# wmrp.net
KiCad netlist of a schematic drawn in EAGLE
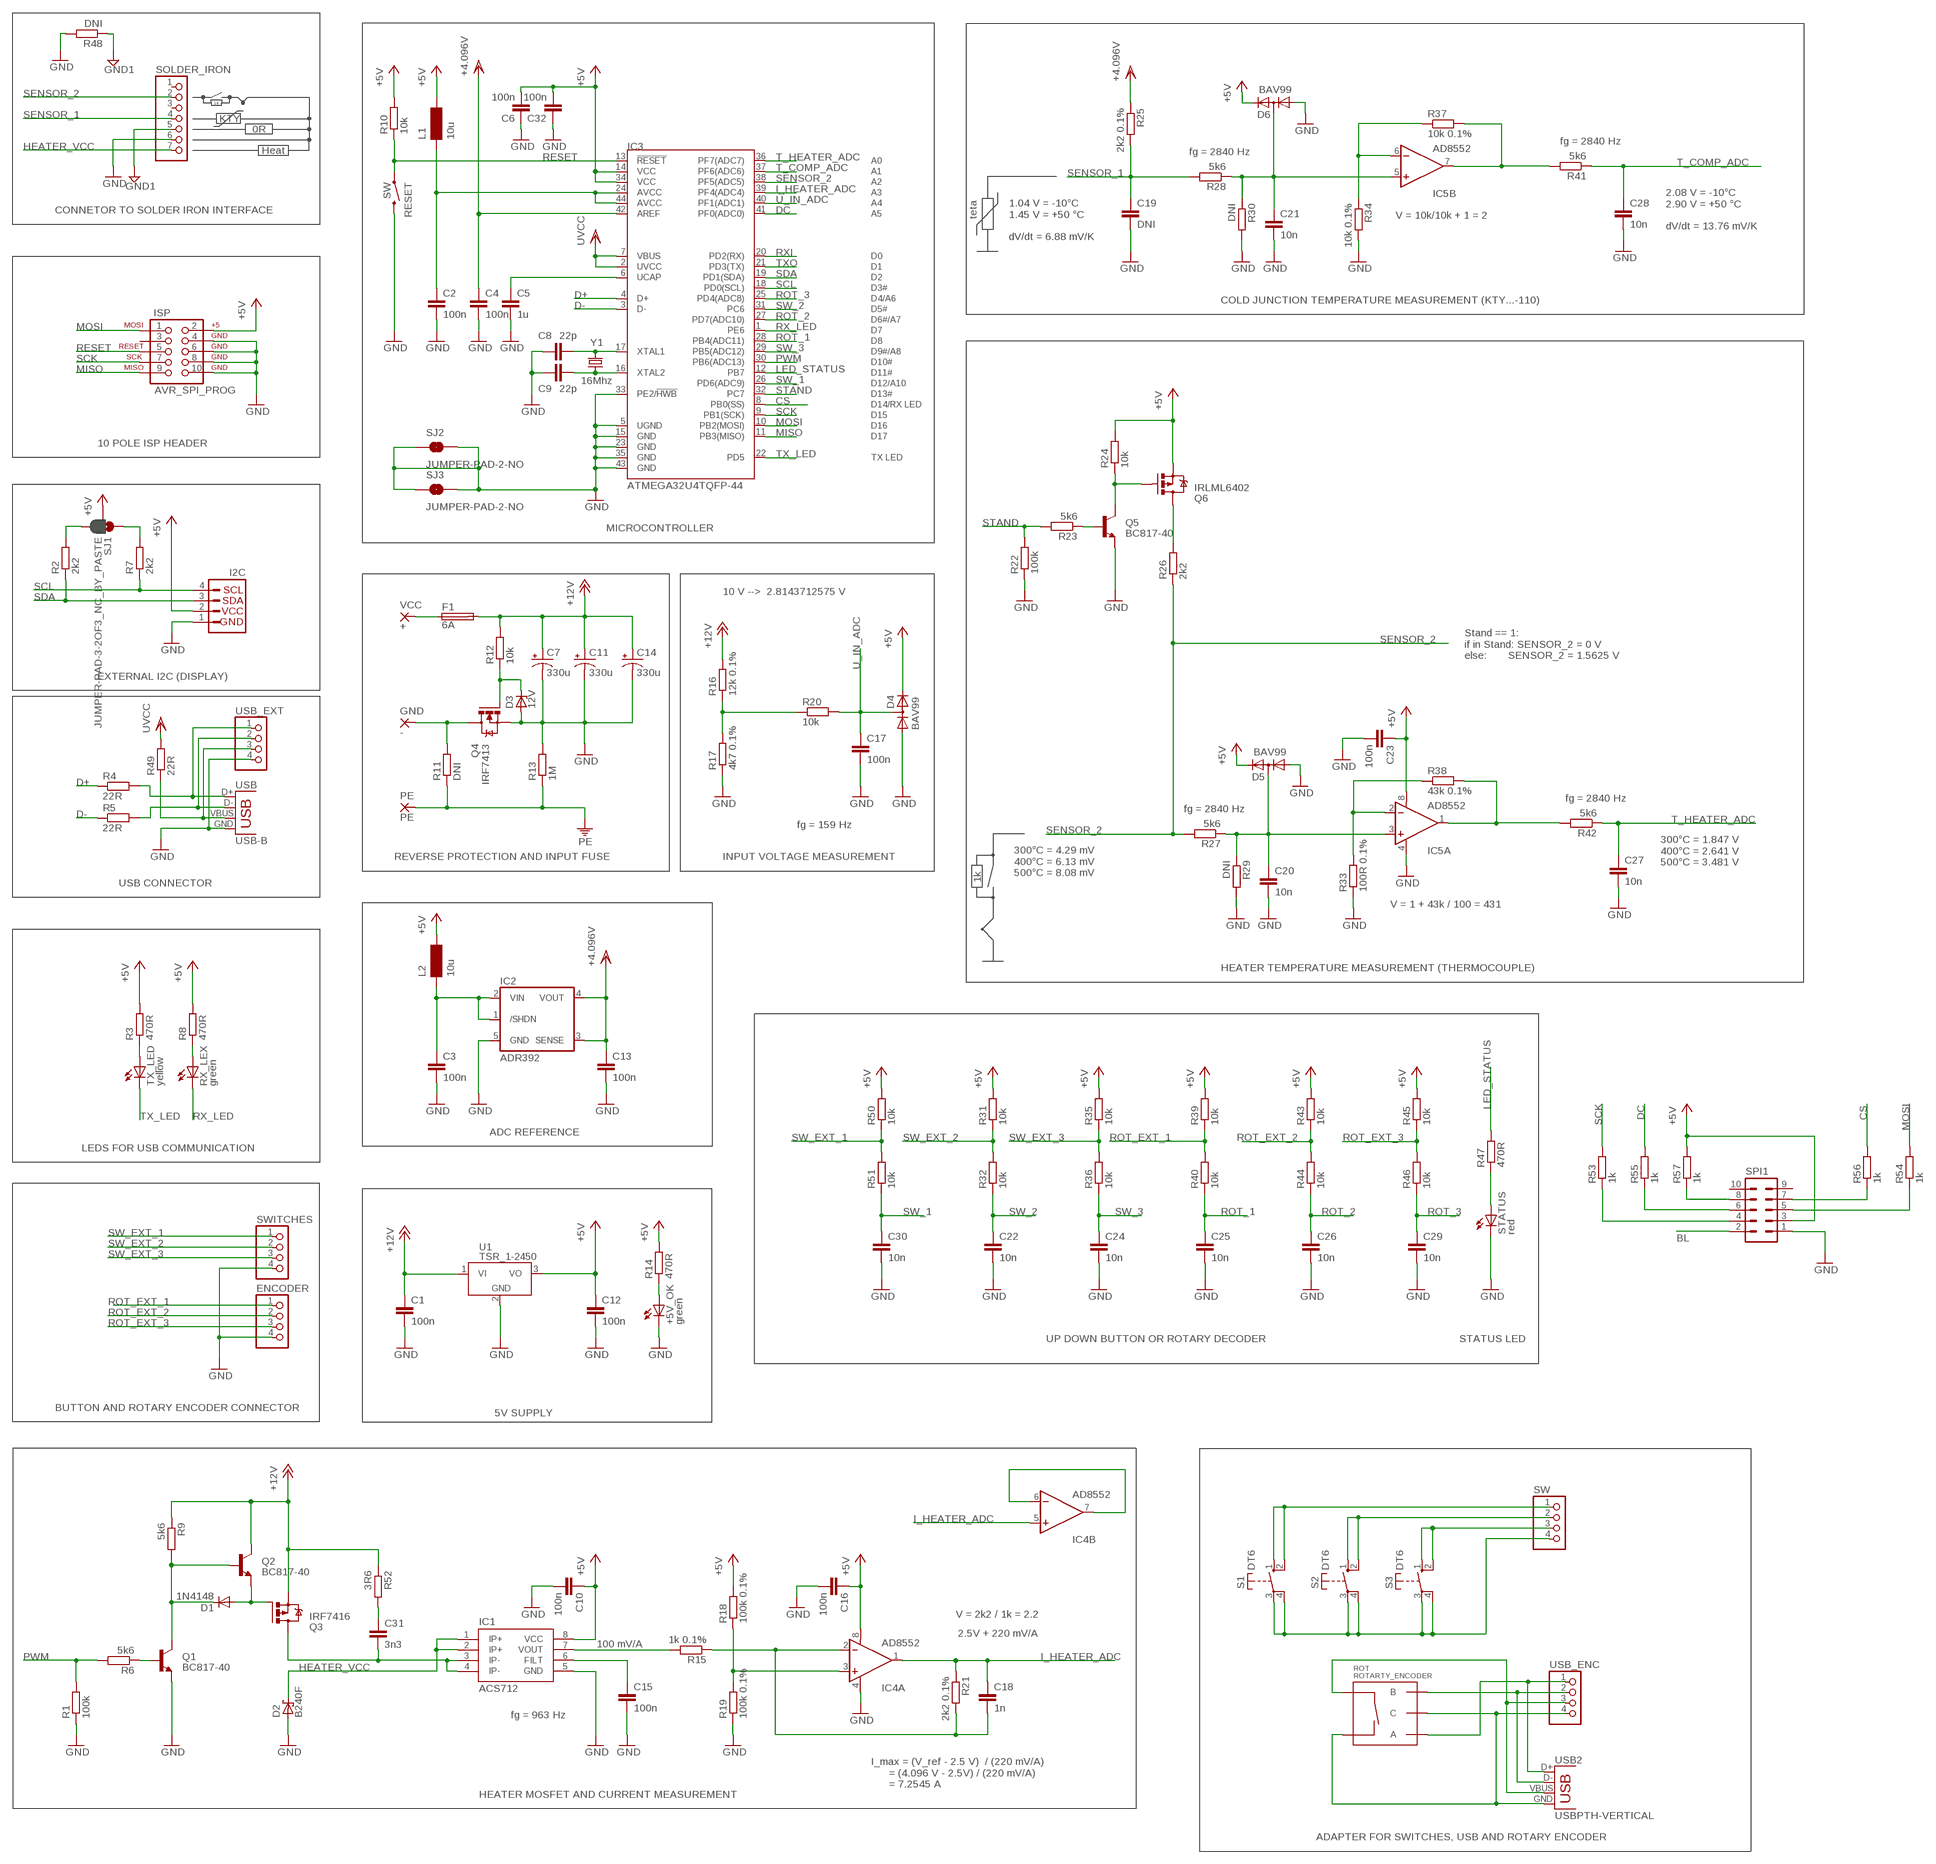
[diagram p0: schematic, sheet 1]

(export (version "E")
  (design (tool "Eeschema 10.0.6"))
  (components
    (comp (ref "+5V_OK")
      (value "green")
      (footprint "eagle-import:CHIPLED_1206")
      (libsource (lib "eagle-import") (part "LEDCHIPLED_1206"))
    )
    (comp (ref "C1")
      (value "100n")
      (footprint "eagle-import:C1206")
      (libsource (lib "eagle-import") (part "resistor_C-EUC1206"))
    )
    (comp (ref "C2")
      (value "100n")
      (footprint "eagle-import:C1206")
      (libsource (lib "eagle-import") (part "resistor_C-EUC1206"))
    )
    (comp (ref "C3")
      (value "100n")
      (footprint "eagle-import:C1206")
      (libsource (lib "eagle-import") (part "resistor_C-EUC1206"))
    )
    (comp (ref "C4")
      (value "100n")
      (footprint "eagle-import:C1206")
      (libsource (lib "eagle-import") (part "resistor_C-EUC1206"))
    )
    (comp (ref "C5")
      (value "1u")
      (footprint "eagle-import:C1206")
      (libsource (lib "eagle-import") (part "resistor_C-EUC1206"))
    )
    (comp (ref "C6")
      (value "100n")
      (footprint "eagle-import:C1206")
      (libsource (lib "eagle-import") (part "resistor_C-EUC1206"))
    )
    (comp (ref "C7")
      (value "330u")
      (footprint "eagle-import:CPOL-RADIAL-1000UF-25V")
      (libsource (lib "eagle-import") (part "CAP_POLPTH4"))
    )
    (comp (ref "C8")
      (value "22p")
      (footprint "eagle-import:C1206")
      (libsource (lib "eagle-import") (part "resistor_C-EUC1206"))
    )
    (comp (ref "C9")
      (value "22p")
      (footprint "eagle-import:C1206")
      (libsource (lib "eagle-import") (part "resistor_C-EUC1206"))
    )
    (comp (ref "C10")
      (value "100n")
      (footprint "eagle-import:C1206")
      (libsource (lib "eagle-import") (part "C-EUC1206"))
    )
    (comp (ref "C11")
      (value "330u")
      (footprint "eagle-import:CPOL-RADIAL-1000UF-25V")
      (libsource (lib "eagle-import") (part "CAP_POLPTH4"))
    )
    (comp (ref "C12")
      (value "100n")
      (footprint "eagle-import:C1206")
      (libsource (lib "eagle-import") (part "resistor_C-EUC1206"))
    )
    (comp (ref "C13")
      (value "100n")
      (footprint "eagle-import:C1206")
      (libsource (lib "eagle-import") (part "resistor_C-EUC1206"))
    )
    (comp (ref "C14")
      (value "330u")
      (footprint "eagle-import:CPOL-RADIAL-1000UF-25V")
      (libsource (lib "eagle-import") (part "CAP_POLPTH4"))
    )
    (comp (ref "C15")
      (value "100n")
      (footprint "eagle-import:C1206")
      (libsource (lib "eagle-import") (part "C-EUC1206"))
    )
    (comp (ref "C16")
      (value "100n")
      (footprint "eagle-import:C1206")
      (libsource (lib "eagle-import") (part "C-EUC1206"))
    )
    (comp (ref "C17")
      (value "100n")
      (footprint "eagle-import:C1206")
      (libsource (lib "eagle-import") (part "resistor_C-EUC1206"))
    )
    (comp (ref "C18")
      (value "1n")
      (footprint "eagle-import:C1206")
      (libsource (lib "eagle-import") (part "C-EUC1206"))
    )
    (comp (ref "C19")
      (value "DNI")
      (footprint "eagle-import:C1206")
      (libsource (lib "eagle-import") (part "C-EUC1206"))
    )
    (comp (ref "C20")
      (value "10n")
      (footprint "eagle-import:C1206")
      (libsource (lib "eagle-import") (part "C-EUC1206"))
    )
    (comp (ref "C21")
      (value "10n")
      (footprint "eagle-import:C1206")
      (libsource (lib "eagle-import") (part "C-EUC1206"))
    )
    (comp (ref "C22")
      (value "10n")
      (footprint "eagle-import:C1206")
      (libsource (lib "eagle-import") (part "C-EUC1206"))
    )
    (comp (ref "C23")
      (value "100n")
      (footprint "eagle-import:C1206")
      (libsource (lib "eagle-import") (part "C-EUC1206"))
    )
    (comp (ref "C24")
      (value "10n")
      (footprint "eagle-import:C1206")
      (libsource (lib "eagle-import") (part "C-EUC1206"))
    )
    (comp (ref "C25")
      (value "10n")
      (footprint "eagle-import:C1206")
      (libsource (lib "eagle-import") (part "C-EUC1206"))
    )
    (comp (ref "C26")
      (value "10n")
      (footprint "eagle-import:C1206")
      (libsource (lib "eagle-import") (part "C-EUC1206"))
    )
    (comp (ref "C27")
      (value "10n")
      (footprint "eagle-import:C1206")
      (libsource (lib "eagle-import") (part "C-EUC1206"))
    )
    (comp (ref "C28")
      (value "10n")
      (footprint "eagle-import:C1206")
      (libsource (lib "eagle-import") (part "C-EUC1206"))
    )
    (comp (ref "C29")
      (value "10n")
      (footprint "eagle-import:C1206")
      (libsource (lib "eagle-import") (part "C-EUC1206"))
    )
    (comp (ref "C30")
      (value "10n")
      (footprint "eagle-import:C1206")
      (libsource (lib "eagle-import") (part "C-EUC1206"))
    )
    (comp (ref "C31")
      (value "3n3")
      (footprint "eagle-import:C1206")
      (libsource (lib "eagle-import") (part "resistor_C-EUC1206"))
    )
    (comp (ref "C32")
      (value "100n")
      (footprint "eagle-import:C1206")
      (libsource (lib "eagle-import") (part "resistor_C-EUC1206"))
    )
    (comp (ref "D1")
      (value "1N4148")
      (footprint "eagle-import:MINIMELF")
      (libsource (lib "eagle-import") (part "DIODE-MINIMELF"))
    )
    (comp (ref "D2")
      (value "B240F")
      (footprint "eagle-import:SMB")
      (libsource (lib "eagle-import") (part "MBRS130LT3"))
    )
    (comp (ref "D3")
      (value "12V")
      (footprint "eagle-import:SOT23")
      (libsource (lib "eagle-import") (part "ZENER-DIODESOT23"))
    )
    (comp (ref "D4")
      (value "BAV99")
      (footprint "eagle-import:SOT23")
      (libsource (lib "eagle-import") (part "BAV99"))
    )
    (comp (ref "D5")
      (value "BAV99")
      (footprint "eagle-import:SOT23")
      (libsource (lib "eagle-import") (part "BAV99"))
    )
    (comp (ref "D6")
      (value "BAV99")
      (footprint "eagle-import:SOT23")
      (libsource (lib "eagle-import") (part "BAV99"))
    )
    (comp (ref "ENCODER")
      (value "PINHD-1X4")
      (footprint "eagle-import:1X04")
      (libsource (lib "eagle-import") (part "PINHD-1X4"))
    )
    (comp (ref "F1")
      (value "6A")
      (footprint "eagle-import:SH22,5")
      (fields (field (name "MF") "SCHURTER") (field (name "MPN") "0031.8201"))
      (libsource (lib "eagle-import") (part "SH22,5"))
    )
    (comp (ref "GND")
      (value "-")
      (footprint "eagle-import:2,2")
      (libsource (lib "eagle-import") (part "2,54/1,0"))
    )
    (comp (ref "I2C")
      (value "I2C_STANDARD")
      (footprint "eagle-import:1X04")
      (libsource (lib "eagle-import") (part "I2C_STANDARD"))
    )
    (comp (ref "IC1")
      (value "ACS712")
      (footprint "eagle-import:SO08")
      (libsource (lib "eagle-import") (part "ACS712"))
    )
    (comp (ref "IC2")
      (value "ADR392")
      (footprint "eagle-import:SOT23-5")
      (libsource (lib "eagle-import") (part "ADR392"))
    )
    (comp (ref "IC3")
      (value "ATMEGA32U4TQFP-44")
      (footprint "eagle-import:TQFP44")
      (libsource (lib "eagle-import") (part "ATMEGA32U4TQFP-44"))
    )
    (comp (ref "IC4")
      (value "AD8552")
      (footprint "eagle-import:SO08")
      (fields (field (name "REICHELT") "AD 8552 AR"))
      (libsource (lib "eagle-import") (part "OPAMP-DUALU"))
    )
    (comp (ref "IC5")
      (value "AD8552")
      (footprint "eagle-import:SO08")
      (fields (field (name "REICHELT") "AD 8552 AR"))
      (libsource (lib "eagle-import") (part "OPAMP-DUALU"))
    )
    (comp (ref "ISP")
      (value "AVR_SPI_PROG")
      (footprint "eagle-import:AVR_ICSP")
      (libsource (lib "eagle-import") (part "AVR_SPI_PROG"))
    )
    (comp (ref "L1")
      (value "10u")
      (footprint "eagle-import:INDUCTOR-1206")
      (libsource (lib "eagle-import") (part "INDUCTORH1206"))
    )
    (comp (ref "L2")
      (value "10u")
      (footprint "eagle-import:INDUCTOR-1206")
      (libsource (lib "eagle-import") (part "INDUCTORH1206"))
    )
    (comp (ref "PE")
      (value "PE")
      (footprint "eagle-import:2,2")
      (libsource (lib "eagle-import") (part "2,54/1,0"))
    )
    (comp (ref "Q1")
      (value "BC817-40")
      (footprint "eagle-import:SOT23-3")
      (libsource (lib "eagle-import") (part "TRANSISTOR_NPNSOT23-3"))
    )
    (comp (ref "Q2")
      (value "BC817-40")
      (footprint "eagle-import:SOT23-3")
      (libsource (lib "eagle-import") (part "TRANSISTOR_NPNSOT23-3"))
    )
    (comp (ref "Q3")
      (value "IRF7416")
      (footprint "eagle-import:SO-08")
      (libsource (lib "eagle-import") (part "IRF7416"))
    )
    (comp (ref "Q4")
      (value "IRF7413")
      (footprint "eagle-import:SO-08")
      (libsource (lib "eagle-import") (part "IRF7413"))
    )
    (comp (ref "Q5")
      (value "BC817-40")
      (footprint "eagle-import:SOT23-3")
      (libsource (lib "eagle-import") (part "TRANSISTOR_NPNSOT23-3"))
    )
    (comp (ref "Q6")
      (value "IRLML6402")
      (footprint "eagle-import:SOT23-3")
      (libsource (lib "eagle-import") (part "MOSFET-PCHANNELSMD"))
    )
    (comp (ref "R1")
      (value "100k")
      (footprint "eagle-import:R1206")
      (libsource (lib "eagle-import") (part "resistor_R-EU_R1206"))
    )
    (comp (ref "R2")
      (value "2k2")
      (footprint "eagle-import:R1206")
      (libsource (lib "eagle-import") (part "resistor_R-EU_R1206"))
    )
    (comp (ref "R3")
      (value "470R")
      (footprint "eagle-import:R1206")
      (libsource (lib "eagle-import") (part "resistor_R-EU_R1206"))
    )
    (comp (ref "R4")
      (value "22R")
      (footprint "eagle-import:R1206")
      (libsource (lib "eagle-import") (part "resistor_R-EU_R1206"))
    )
    (comp (ref "R5")
      (value "22R")
      (footprint "eagle-import:R1206")
      (libsource (lib "eagle-import") (part "resistor_R-EU_R1206"))
    )
    (comp (ref "R6")
      (value "5k6")
      (footprint "eagle-import:M1206")
      (libsource (lib "eagle-import") (part "R-EU_M1206"))
    )
    (comp (ref "R7")
      (value "2k2")
      (footprint "eagle-import:R1206")
      (libsource (lib "eagle-import") (part "resistor_R-EU_R1206"))
    )
    (comp (ref "R8")
      (value "470R")
      (footprint "eagle-import:R1206")
      (libsource (lib "eagle-import") (part "resistor_R-EU_R1206"))
    )
    (comp (ref "R9")
      (value "5k6")
      (footprint "eagle-import:M1206")
      (libsource (lib "eagle-import") (part "R-EU_M1206"))
    )
    (comp (ref "R10")
      (value "10k")
      (footprint "eagle-import:R1206")
      (libsource (lib "eagle-import") (part "resistor_R-EU_R1206"))
    )
    (comp (ref "R11")
      (value "DNI")
      (footprint "eagle-import:R1206")
      (libsource (lib "eagle-import") (part "resistor_R-EU_R1206"))
    )
    (comp (ref "R12")
      (value "10k")
      (footprint "eagle-import:R1206")
      (libsource (lib "eagle-import") (part "resistor_R-EU_R1206"))
    )
    (comp (ref "R13")
      (value "1M")
      (footprint "eagle-import:R1206")
      (libsource (lib "eagle-import") (part "resistor_R-EU_R1206"))
    )
    (comp (ref "R14")
      (value "470R")
      (footprint "eagle-import:R1206")
      (libsource (lib "eagle-import") (part "resistor_R-EU_R1206"))
    )
    (comp (ref "R15")
      (value "1k 0.1%")
      (footprint "eagle-import:M1206")
      (libsource (lib "eagle-import") (part "R-EU_M1206"))
    )
    (comp (ref "R16")
      (value "12k 0.1%")
      (footprint "eagle-import:R1206")
      (libsource (lib "eagle-import") (part "resistor_R-EU_R1206"))
    )
    (comp (ref "R17")
      (value "4k7 0.1%")
      (footprint "eagle-import:R1206")
      (libsource (lib "eagle-import") (part "resistor_R-EU_R1206"))
    )
    (comp (ref "R18")
      (value "100k 0.1%")
      (footprint "eagle-import:M1206")
      (libsource (lib "eagle-import") (part "R-EU_M1206"))
    )
    (comp (ref "R19")
      (value "100k 0.1%")
      (footprint "eagle-import:M1206")
      (libsource (lib "eagle-import") (part "R-EU_M1206"))
    )
    (comp (ref "R20")
      (value "10k")
      (footprint "eagle-import:R1206")
      (libsource (lib "eagle-import") (part "resistor_R-EU_R1206"))
    )
    (comp (ref "R21")
      (value "2k2 0.1%")
      (footprint "eagle-import:M1206")
      (libsource (lib "eagle-import") (part "R-EU_M1206"))
    )
    (comp (ref "R22")
      (value "100k")
      (footprint "eagle-import:R1206")
      (libsource (lib "eagle-import") (part "resistor_R-EU_R1206"))
    )
    (comp (ref "R23")
      (value "5k6")
      (footprint "eagle-import:M1206")
      (libsource (lib "eagle-import") (part "R-EU_M1206"))
    )
    (comp (ref "R24")
      (value "10k")
      (footprint "eagle-import:R1206")
      (libsource (lib "eagle-import") (part "resistor_R-EU_R1206"))
    )
    (comp (ref "R25")
      (value "2k2 0.1%")
      (footprint "eagle-import:M1206")
      (libsource (lib "eagle-import") (part "R-EU_M1206"))
    )
    (comp (ref "R26")
      (value "2k2")
      (footprint "eagle-import:R1206")
      (libsource (lib "eagle-import") (part "resistor_R-EU_R1206"))
    )
    (comp (ref "R27")
      (value "5k6")
      (footprint "eagle-import:M1206")
      (libsource (lib "eagle-import") (part "R-EU_M1206"))
    )
    (comp (ref "R28")
      (value "5k6")
      (footprint "eagle-import:M1206")
      (libsource (lib "eagle-import") (part "R-EU_M1206"))
    )
    (comp (ref "R29")
      (value "DNI")
      (footprint "eagle-import:M1206")
      (libsource (lib "eagle-import") (part "R-EU_M1206"))
    )
    (comp (ref "R30")
      (value "DNI")
      (footprint "eagle-import:M1206")
      (libsource (lib "eagle-import") (part "R-EU_M1206"))
    )
    (comp (ref "R31")
      (value "10k")
      (footprint "eagle-import:R1206")
      (libsource (lib "eagle-import") (part "resistor_R-EU_R1206"))
    )
    (comp (ref "R32")
      (value "10k")
      (footprint "eagle-import:R1206")
      (libsource (lib "eagle-import") (part "resistor_R-EU_R1206"))
    )
    (comp (ref "R33")
      (value "100R 0.1%")
      (footprint "eagle-import:M1206")
      (libsource (lib "eagle-import") (part "R-EU_M1206"))
    )
    (comp (ref "R34")
      (value "10k 0.1%")
      (footprint "eagle-import:M1206")
      (libsource (lib "eagle-import") (part "R-EU_M1206"))
    )
    (comp (ref "R35")
      (value "10k")
      (footprint "eagle-import:R1206")
      (libsource (lib "eagle-import") (part "resistor_R-EU_R1206"))
    )
    (comp (ref "R36")
      (value "10k")
      (footprint "eagle-import:R1206")
      (libsource (lib "eagle-import") (part "resistor_R-EU_R1206"))
    )
    (comp (ref "R37")
      (value "10k 0.1%")
      (footprint "eagle-import:M1206")
      (libsource (lib "eagle-import") (part "R-EU_M1206"))
    )
    (comp (ref "R38")
      (value "43k 0.1%")
      (footprint "eagle-import:M1206")
      (libsource (lib "eagle-import") (part "R-EU_M1206"))
    )
    (comp (ref "R39")
      (value "10k")
      (footprint "eagle-import:R1206")
      (libsource (lib "eagle-import") (part "resistor_R-EU_R1206"))
    )
    (comp (ref "R40")
      (value "10k")
      (footprint "eagle-import:R1206")
      (libsource (lib "eagle-import") (part "resistor_R-EU_R1206"))
    )
    (comp (ref "R41")
      (value "5k6")
      (footprint "eagle-import:M1206")
      (libsource (lib "eagle-import") (part "R-EU_M1206"))
    )
    (comp (ref "R42")
      (value "5k6")
      (footprint "eagle-import:M1206")
      (libsource (lib "eagle-import") (part "R-EU_M1206"))
    )
    (comp (ref "R43")
      (value "10k")
      (footprint "eagle-import:R1206")
      (libsource (lib "eagle-import") (part "resistor_R-EU_R1206"))
    )
    (comp (ref "R44")
      (value "10k")
      (footprint "eagle-import:R1206")
      (libsource (lib "eagle-import") (part "resistor_R-EU_R1206"))
    )
    (comp (ref "R45")
      (value "10k")
      (footprint "eagle-import:R1206")
      (libsource (lib "eagle-import") (part "resistor_R-EU_R1206"))
    )
    (comp (ref "R46")
      (value "10k")
      (footprint "eagle-import:R1206")
      (libsource (lib "eagle-import") (part "resistor_R-EU_R1206"))
    )
    (comp (ref "R47")
      (value "470R")
      (footprint "eagle-import:R1206")
      (libsource (lib "eagle-import") (part "resistor_R-EU_R1206"))
    )
    (comp (ref "R48")
      (value "DNI")
      (footprint "eagle-import:R1206")
      (libsource (lib "eagle-import") (part "resistor_R-EU_R1206"))
    )
    (comp (ref "R49")
      (value "22R")
      (footprint "eagle-import:R1206")
      (libsource (lib "eagle-import") (part "resistor_R-EU_R1206"))
    )
    (comp (ref "R50")
      (value "10k")
      (footprint "eagle-import:R1206")
      (libsource (lib "eagle-import") (part "resistor_R-EU_R1206"))
    )
    (comp (ref "R51")
      (value "10k")
      (footprint "eagle-import:R1206")
      (libsource (lib "eagle-import") (part "resistor_R-EU_R1206"))
    )
    (comp (ref "R52")
      (value "3R6")
      (footprint "eagle-import:M1206")
      (libsource (lib "eagle-import") (part "R-EU_M1206"))
    )
    (comp (ref "R53")
      (value "1k")
      (footprint "eagle-import:R1206")
      (libsource (lib "eagle-import") (part "resistor_R-EU_R1206"))
    )
    (comp (ref "R54")
      (value "1k")
      (footprint "eagle-import:R1206")
      (libsource (lib "eagle-import") (part "resistor_R-EU_R1206"))
    )
    (comp (ref "R55")
      (value "1k")
      (footprint "eagle-import:R1206")
      (libsource (lib "eagle-import") (part "resistor_R-EU_R1206"))
    )
    (comp (ref "R56")
      (value "1k")
      (footprint "eagle-import:R1206")
      (libsource (lib "eagle-import") (part "resistor_R-EU_R1206"))
    )
    (comp (ref "R57")
      (value "1k")
      (footprint "eagle-import:R1206")
      (libsource (lib "eagle-import") (part "resistor_R-EU_R1206"))
    )
    (comp (ref "RESET")
      (value "SW")
      (footprint "eagle-import:TACTILE-PTH")
      (libsource (lib "eagle-import") (part "SWITCH-MOMENTARY-2PTH"))
    )
    (comp (ref "ROT")
      (value "ROTARTY_ENCODER")
      (footprint "eagle-import:ROTARY_ENC_PLAIN")
      (libsource (lib "eagle-import") (part "ROTARTY_ENCODER"))
    )
    (comp (ref "RX_LEX")
      (value "green")
      (footprint "eagle-import:CHIPLED_1206")
      (libsource (lib "eagle-import") (part "LEDCHIPLED_1206"))
    )
    (comp (ref "S1")
      (value "DT6")
      (footprint "eagle-import:DT6")
      (libsource (lib "eagle-import") (part "DT6"))
    )
    (comp (ref "S2")
      (value "DT6")
      (footprint "eagle-import:DT6")
      (libsource (lib "eagle-import") (part "DT6"))
    )
    (comp (ref "S3")
      (value "DT6")
      (footprint "eagle-import:DT6")
      (libsource (lib "eagle-import") (part "DT6"))
    )
    (comp (ref "SJ1")
      (value "JUMPER-PAD-3-2OF3_NC_BY_PASTE")
      (footprint "eagle-import:PAD-JUMPER-3-2OF3_NC_BY_PASTE_YES_SILK_FULL_BOX")
      (libsource (lib "eagle-import") (part "JUMPER-PAD-3-2OF3_NC_BY_PASTE"))
    )
    (comp (ref "SJ2")
      (value "JUMPER-PAD-2-NO")
      (footprint "eagle-import:PAD-JUMPER-2-NO_NO_SILK")
      (libsource (lib "eagle-import") (part "JUMPER-PAD-2-NO"))
    )
    (comp (ref "SJ3")
      (value "JUMPER-PAD-2-NO")
      (footprint "eagle-import:PAD-JUMPER-2-NO_NO_SILK")
      (libsource (lib "eagle-import") (part "JUMPER-PAD-2-NO"))
    )
    (comp (ref "SOLDER_IRON")
      (value "PINHD-1X7")
      (footprint "eagle-import:1X07")
      (libsource (lib "eagle-import") (part "PINHD-1X7"))
    )
    (comp (ref "SPI1")
      (value "MA05-2")
      (footprint "eagle-import:MA05-2")
      (libsource (lib "eagle-import") (part "MA05-2"))
    )
    (comp (ref "STATUS")
      (value "red")
      (footprint "eagle-import:CHIPLED_1206")
      (libsource (lib "eagle-import") (part "LEDCHIPLED_1206"))
    )
    (comp (ref "SW")
      (value "PINHD-1X4")
      (footprint "eagle-import:1X04")
      (libsource (lib "eagle-import") (part "PINHD-1X4"))
    )
    (comp (ref "SWITCHES")
      (value "PINHD-1X4")
      (footprint "eagle-import:1X04")
      (libsource (lib "eagle-import") (part "PINHD-1X4"))
    )
    (comp (ref "TX_LED")
      (value "yellow")
      (footprint "eagle-import:CHIPLED_1206")
      (libsource (lib "eagle-import") (part "LEDCHIPLED_1206"))
    )
    (comp (ref "U1")
      (value "TSR_1-2450")
      (footprint "eagle-import:TSR-1")
      (libsource (lib "eagle-import") (part "TSR_1-2450"))
    )
    (comp (ref "USB")
      (value "USB-B")
      (footprint "eagle-import:USB-B-PTH")
      (libsource (lib "eagle-import") (part "USBPTH"))
    )
    (comp (ref "USB2")
      (value "USBPTH-VERTICAL")
      (footprint "eagle-import:USB-B-PTH-VERTICAL")
      (libsource (lib "eagle-import") (part "wmrp_USBPTH-VERTICAL"))
    )
    (comp (ref "USB_ENC")
      (value "PINHD-1X4")
      (footprint "eagle-import:1X04")
      (libsource (lib "eagle-import") (part "PINHD-1X4"))
    )
    (comp (ref "USB_EXT")
      (value "PINHD-1X4")
      (footprint "eagle-import:1X04")
      (libsource (lib "eagle-import") (part "PINHD-1X4"))
    )
    (comp (ref "VCC")
      (value "+")
      (footprint "eagle-import:2,2")
      (libsource (lib "eagle-import") (part "2,54/1,0"))
    )
    (comp (ref "Y1")
      (value "16Mhz")
      (footprint "eagle-import:HC49US")
      (libsource (lib "eagle-import") (part "CRYSTALHC49US"))
    )
  )
  (nets
    (net (code "1") (name "+4.096V") (class "Default")
      (node (ref "C13") (pin "1") (pinfunction "1_1") (pintype "passive"))
      (node (ref "C4") (pin "1") (pinfunction "1_1") (pintype "passive"))
      (node (ref "IC2") (pin "3") (pinfunction "SENSE_3") (pintype "input"))
      (node (ref "IC2") (pin "4") (pinfunction "VOUT_4") (pintype "output"))
      (node (ref "IC3") (pin "42") (pinfunction "AREF_42") (pintype "bidirectional"))
      (node (ref "R25") (pin "1") (pinfunction "1_1") (pintype "passive"))
    )
    (net (code "2") (name "+5V") (class "Default")
      (node (ref "C10") (pin "1") (pinfunction "1_1") (pintype "passive"))
      (node (ref "C12") (pin "1") (pinfunction "1_1") (pintype "passive"))
      (node (ref "C16") (pin "1") (pinfunction "1_1") (pintype "passive"))
      (node (ref "C23") (pin "1") (pinfunction "1_1") (pintype "passive"))
      (node (ref "C32") (pin "2") (pinfunction "2_2") (pintype "passive"))
      (node (ref "C6") (pin "2") (pinfunction "2_2") (pintype "passive"))
      (node (ref "D4") (pin "2") (pinfunction "C2_2") (pintype "passive"))
      (node (ref "D5") (pin "2") (pinfunction "C2_2") (pintype "passive"))
      (node (ref "D6") (pin "2") (pinfunction "C2_2") (pintype "passive"))
      (node (ref "I2C") (pin "2") (pinfunction "2_2") (pintype "passive"))
      (node (ref "IC1") (pin "8") (pinfunction "VCC_8") (pintype "bidirectional"))
      (node (ref "IC3") (pin "14") (pinfunction "VCC_14") (pintype "bidirectional"))
      (node (ref "IC3") (pin "34") (pinfunction "VCC_34") (pintype "bidirectional"))
      (node (ref "IC4") (pin "8") (pinfunction "V+_8") (pintype "power_in"))
      (node (ref "IC5") (pin "8") (pinfunction "V+_8") (pintype "power_in"))
      (node (ref "ISP") (pin "2") (pinfunction "2_2") (pintype "passive"))
      (node (ref "L1") (pin "P$1") (pinfunction "1_P$1") (pintype "passive"))
      (node (ref "L2") (pin "P$1") (pinfunction "1_P$1") (pintype "passive"))
      (node (ref "Q6") (pin "2") (pinfunction "S_2") (pintype "passive"))
      (node (ref "R10") (pin "2") (pinfunction "2_2") (pintype "passive"))
      (node (ref "R14") (pin "2") (pinfunction "2_2") (pintype "passive"))
      (node (ref "R18") (pin "2") (pinfunction "2_2") (pintype "passive"))
      (node (ref "R24") (pin "2") (pinfunction "2_2") (pintype "passive"))
      (node (ref "R3") (pin "2") (pinfunction "2_2") (pintype "passive"))
      (node (ref "R31") (pin "2") (pinfunction "2_2") (pintype "passive"))
      (node (ref "R35") (pin "2") (pinfunction "2_2") (pintype "passive"))
      (node (ref "R39") (pin "2") (pinfunction "2_2") (pintype "passive"))
      (node (ref "R43") (pin "2") (pinfunction "2_2") (pintype "passive"))
      (node (ref "R45") (pin "2") (pinfunction "2_2") (pintype "passive"))
      (node (ref "R50") (pin "2") (pinfunction "2_2") (pintype "passive"))
      (node (ref "R57") (pin "2") (pinfunction "2_2") (pintype "passive"))
      (node (ref "R8") (pin "2") (pinfunction "2_2") (pintype "passive"))
      (node (ref "SJ1") (pin "2") (pinfunction "2_2") (pintype "passive"))
      (node (ref "SPI1") (pin "3") (pinfunction "3_3") (pintype "passive"))
      (node (ref "U1") (pin "3") (pinfunction "VO_3") (pintype "power_in"))
    )
    (net (code "3") (name "+12V") (class "Default")
      (node (ref "C1") (pin "1") (pinfunction "1_1") (pintype "passive"))
      (node (ref "C11") (pin "1") (pinfunction "+_1") (pintype "passive"))
      (node (ref "C14") (pin "1") (pinfunction "+_1") (pintype "passive"))
      (node (ref "C7") (pin "1") (pinfunction "+_1") (pintype "passive"))
      (node (ref "F1") (pin "2") (pinfunction "2_2") (pintype "passive"))
      (node (ref "Q2") (pin "3") (pinfunction "C_3") (pintype "passive"))
      (node (ref "Q3") (pin "1") (pinfunction "S_1") (pintype "passive"))
      (node (ref "Q3") (pin "2") (pinfunction "S_2") (pintype "passive"))
      (node (ref "Q3") (pin "3") (pinfunction "S_3") (pintype "passive"))
      (node (ref "R12") (pin "2") (pinfunction "2_2") (pintype "passive"))
      (node (ref "R16") (pin "2") (pinfunction "2_2") (pintype "passive"))
      (node (ref "R52") (pin "1") (pinfunction "1_1") (pintype "passive"))
      (node (ref "R9") (pin "1") (pinfunction "1_1") (pintype "passive"))
      (node (ref "U1") (pin "1") (pinfunction "VI_1") (pintype "power_in"))
    )
    (net (code "4") (name "/BL") (class "Default")
      (node (ref "SPI1") (pin "2") (pinfunction "2_2") (pintype "passive"))
    )
    (net (code "5") (name "/CS") (class "Default")
      (node (ref "IC3") (pin "8") (pinfunction "PB0(SS)_8") (pintype "bidirectional"))
      (node (ref "R56") (pin "2") (pinfunction "2_2") (pintype "passive"))
    )
    (net (code "6") (name "/D+") (class "Default")
      (node (ref "IC3") (pin "4") (pinfunction "D+_4") (pintype "bidirectional"))
      (node (ref "R4") (pin "1") (pinfunction "1_1") (pintype "passive"))
    )
    (net (code "7") (name "/D-") (class "Default")
      (node (ref "IC3") (pin "3") (pinfunction "D-_3") (pintype "bidirectional"))
      (node (ref "R5") (pin "1") (pinfunction "1_1") (pintype "passive"))
    )
    (net (code "8") (name "/DC") (class "Default")
      (node (ref "IC3") (pin "41") (pinfunction "PF0(ADC0)_41") (pintype "bidirectional"))
      (node (ref "R55") (pin "2") (pinfunction "2_2") (pintype "passive"))
    )
    (net (code "9") (name "/HEATER_VCC") (class "Default")
      (node (ref "D2") (pin "C") (pinfunction "C_C") (pintype "passive"))
      (node (ref "IC1") (pin "1") (pinfunction "IP+_1") (pintype "bidirectional"))
      (node (ref "IC1") (pin "2") (pinfunction "IP+_2") (pintype "bidirectional"))
      (node (ref "SOLDER_IRON") (pin "7") (pinfunction "7_7") (pintype "passive"))
    )
    (net (code "10") (name "/I_HEATER_ADC") (class "Default")
      (node (ref "C18") (pin "1") (pinfunction "1_1") (pintype "passive"))
      (node (ref "IC3") (pin "39") (pinfunction "PF4(ADC4)_39") (pintype "bidirectional"))
      (node (ref "IC4") (pin "1") (pinfunction "OUT_1") (pintype "output"))
      (node (ref "IC4") (pin "5") (pinfunction "+IN_5") (pintype "input"))
      (node (ref "R21") (pin "1") (pinfunction "1_1") (pintype "passive"))
    )
    (net (code "11") (name "/LED_STATUS") (class "Default")
      (node (ref "IC3") (pin "12") (pinfunction "PB7_12") (pintype "bidirectional"))
      (node (ref "R47") (pin "2") (pinfunction "2_2") (pintype "passive"))
    )
    (net (code "12") (name "/MISO") (class "Default")
      (node (ref "IC3") (pin "11") (pinfunction "PB3(MISO)_11") (pintype "bidirectional"))
      (node (ref "ISP") (pin "9") (pinfunction "9_9") (pintype "passive"))
    )
    (net (code "13") (name "/MOSI") (class "Default")
      (node (ref "IC3") (pin "10") (pinfunction "PB2(MOSI)_10") (pintype "bidirectional"))
      (node (ref "ISP") (pin "1") (pinfunction "1_1") (pintype "passive"))
      (node (ref "R54") (pin "2") (pinfunction "2_2") (pintype "passive"))
    )
    (net (code "14") (name "/PWM") (class "Default")
      (node (ref "IC3") (pin "30") (pinfunction "PB6(ADC13)_30") (pintype "bidirectional"))
      (node (ref "R1") (pin "2") (pinfunction "2_2") (pintype "passive"))
      (node (ref "R6") (pin "2") (pinfunction "2_2") (pintype "passive"))
    )
    (net (code "15") (name "/RESET") (class "Default")
      (node (ref "IC3") (pin "13") (pinfunction "~{RESET}_13") (pintype "bidirectional"))
      (node (ref "ISP") (pin "5") (pinfunction "5_5") (pintype "passive"))
      (node (ref "R10") (pin "1") (pinfunction "1_1") (pintype "passive"))
      (node (ref "RESET") (pin "1") (pinfunction "1_1") (pintype "passive"))
    )
    (net (code "16") (name "/ROT_1") (class "Default")
      (node (ref "C25") (pin "1") (pinfunction "1_1") (pintype "passive"))
      (node (ref "IC3") (pin "28") (pinfunction "PB4(ADC11)_28") (pintype "bidirectional"))
      (node (ref "R40") (pin "1") (pinfunction "1_1") (pintype "passive"))
    )
    (net (code "17") (name "/ROT_2") (class "Default")
      (node (ref "C26") (pin "1") (pinfunction "1_1") (pintype "passive"))
      (node (ref "IC3") (pin "27") (pinfunction "PD7(ADC10)_27") (pintype "bidirectional"))
      (node (ref "R44") (pin "1") (pinfunction "1_1") (pintype "passive"))
    )
    (net (code "18") (name "/ROT_3") (class "Default")
      (node (ref "C29") (pin "1") (pinfunction "1_1") (pintype "passive"))
      (node (ref "IC3") (pin "25") (pinfunction "PD4(ADC8)_25") (pintype "bidirectional"))
      (node (ref "R46") (pin "1") (pinfunction "1_1") (pintype "passive"))
    )
    (net (code "19") (name "/ROT_EXT_1") (class "Default")
      (node (ref "ENCODER") (pin "1") (pinfunction "1_1") (pintype "passive"))
      (node (ref "R39") (pin "1") (pinfunction "1_1") (pintype "passive"))
      (node (ref "R40") (pin "2") (pinfunction "2_2") (pintype "passive"))
    )
    (net (code "20") (name "/ROT_EXT_2") (class "Default")
      (node (ref "ENCODER") (pin "2") (pinfunction "2_2") (pintype "passive"))
      (node (ref "R43") (pin "1") (pinfunction "1_1") (pintype "passive"))
      (node (ref "R44") (pin "2") (pinfunction "2_2") (pintype "passive"))
    )
    (net (code "21") (name "/ROT_EXT_3") (class "Default")
      (node (ref "ENCODER") (pin "3") (pinfunction "3_3") (pintype "passive"))
      (node (ref "R45") (pin "1") (pinfunction "1_1") (pintype "passive"))
      (node (ref "R46") (pin "2") (pinfunction "2_2") (pintype "passive"))
    )
    (net (code "22") (name "/RXI") (class "Default")
      (node (ref "IC3") (pin "20") (pinfunction "PD2(RX)_20") (pintype "bidirectional"))
    )
    (net (code "23") (name "/RX_LED") (class "Default")
      (node (ref "IC3") (pin "1") (pinfunction "PE6_1") (pintype "bidirectional"))
      (node (ref "RX_LEX") (pin "C") (pinfunction "C_C") (pintype "passive"))
    )
    (net (code "24") (name "/SCK") (class "Default")
      (node (ref "IC3") (pin "9") (pinfunction "PB1(SCK)_9") (pintype "bidirectional"))
      (node (ref "ISP") (pin "7") (pinfunction "7_7") (pintype "passive"))
      (node (ref "R53") (pin "2") (pinfunction "2_2") (pintype "passive"))
    )
    (net (code "25") (name "/SCL") (class "Default")
      (node (ref "I2C") (pin "4") (pinfunction "4_4") (pintype "passive"))
      (node (ref "IC3") (pin "18") (pinfunction "PD0(SCL)_18") (pintype "bidirectional"))
      (node (ref "R7") (pin "1") (pinfunction "1_1") (pintype "passive"))
    )
    (net (code "26") (name "/SDA") (class "Default")
      (node (ref "I2C") (pin "3") (pinfunction "3_3") (pintype "passive"))
      (node (ref "IC3") (pin "19") (pinfunction "PD1(SDA)_19") (pintype "bidirectional"))
      (node (ref "R2") (pin "1") (pinfunction "1_1") (pintype "passive"))
    )
    (net (code "27") (name "/SENSOR_1") (class "Default")
      (node (ref "C19") (pin "1") (pinfunction "1_1") (pintype "passive"))
      (node (ref "R25") (pin "2") (pinfunction "2_2") (pintype "passive"))
      (node (ref "R28") (pin "2") (pinfunction "2_2") (pintype "passive"))
      (node (ref "SOLDER_IRON") (pin "4") (pinfunction "4_4") (pintype "passive"))
    )
    (net (code "28") (name "/SENSOR_2") (class "Default")
      (node (ref "IC3") (pin "38") (pinfunction "PF5(ADC5)_38") (pintype "bidirectional"))
      (node (ref "R26") (pin "1") (pinfunction "1_1") (pintype "passive"))
      (node (ref "R27") (pin "2") (pinfunction "2_2") (pintype "passive"))
      (node (ref "SOLDER_IRON") (pin "2") (pinfunction "2_2") (pintype "passive"))
    )
    (net (code "29") (name "/STAND") (class "Default")
      (node (ref "IC3") (pin "32") (pinfunction "PC7_32") (pintype "bidirectional"))
      (node (ref "R22") (pin "2") (pinfunction "2_2") (pintype "passive"))
      (node (ref "R23") (pin "2") (pinfunction "2_2") (pintype "passive"))
    )
    (net (code "30") (name "/SW_1") (class "Default")
      (node (ref "C30") (pin "1") (pinfunction "1_1") (pintype "passive"))
      (node (ref "IC3") (pin "26") (pinfunction "PD6(ADC9)_26") (pintype "bidirectional"))
      (node (ref "R51") (pin "1") (pinfunction "1_1") (pintype "passive"))
    )
    (net (code "31") (name "/SW_2") (class "Default")
      (node (ref "C22") (pin "1") (pinfunction "1_1") (pintype "passive"))
      (node (ref "IC3") (pin "31") (pinfunction "PC6_31") (pintype "bidirectional"))
      (node (ref "R32") (pin "1") (pinfunction "1_1") (pintype "passive"))
    )
    (net (code "32") (name "/SW_3") (class "Default")
      (node (ref "C24") (pin "1") (pinfunction "1_1") (pintype "passive"))
      (node (ref "IC3") (pin "29") (pinfunction "PB5(ADC12)_29") (pintype "bidirectional"))
      (node (ref "R36") (pin "1") (pinfunction "1_1") (pintype "passive"))
    )
    (net (code "33") (name "/SW_EXT_1") (class "Default")
      (node (ref "R50") (pin "1") (pinfunction "1_1") (pintype "passive"))
      (node (ref "R51") (pin "2") (pinfunction "2_2") (pintype "passive"))
      (node (ref "SWITCHES") (pin "1") (pinfunction "1_1") (pintype "passive"))
    )
    (net (code "34") (name "/SW_EXT_2") (class "Default")
      (node (ref "R31") (pin "1") (pinfunction "1_1") (pintype "passive"))
      (node (ref "R32") (pin "2") (pinfunction "2_2") (pintype "passive"))
      (node (ref "SWITCHES") (pin "2") (pinfunction "2_2") (pintype "passive"))
    )
    (net (code "35") (name "/SW_EXT_3") (class "Default")
      (node (ref "R35") (pin "1") (pinfunction "1_1") (pintype "passive"))
      (node (ref "R36") (pin "2") (pinfunction "2_2") (pintype "passive"))
      (node (ref "SWITCHES") (pin "3") (pinfunction "3_3") (pintype "passive"))
    )
    (net (code "36") (name "/TXO") (class "Default")
      (node (ref "IC3") (pin "21") (pinfunction "PD3(TX)_21") (pintype "bidirectional"))
    )
    (net (code "37") (name "/TX_LED") (class "Default")
      (node (ref "IC3") (pin "22") (pinfunction "PD5_22") (pintype "bidirectional"))
      (node (ref "TX_LED") (pin "C") (pinfunction "C_C") (pintype "passive"))
    )
    (net (code "38") (name "/T_COMP_ADC") (class "Default")
      (node (ref "C28") (pin "1") (pinfunction "1_1") (pintype "passive"))
      (node (ref "IC3") (pin "37") (pinfunction "PF6(ADC6)_37") (pintype "bidirectional"))
      (node (ref "R41") (pin "1") (pinfunction "1_1") (pintype "passive"))
    )
    (net (code "39") (name "/T_HEATER_ADC") (class "Default")
      (node (ref "C27") (pin "1") (pinfunction "1_1") (pintype "passive"))
      (node (ref "IC3") (pin "36") (pinfunction "PF7(ADC7)_36") (pintype "bidirectional"))
      (node (ref "R42") (pin "1") (pinfunction "1_1") (pintype "passive"))
    )
    (net (code "40") (name "/U_IN_ADC") (class "Default")
      (node (ref "C17") (pin "1") (pinfunction "1_1") (pintype "passive"))
      (node (ref "D4") (pin "3") (pinfunction "C1A2_3") (pintype "passive"))
      (node (ref "IC3") (pin "40") (pinfunction "PF1(ADC1)_40") (pintype "bidirectional"))
      (node (ref "R20") (pin "2") (pinfunction "2_2") (pintype "passive"))
    )
    (net (code "41") (name "GND") (class "Default")
      (node (ref "+5V_OK") (pin "C") (pinfunction "C_C") (pintype "passive"))
      (node (ref "C1") (pin "2") (pinfunction "2_2") (pintype "passive"))
      (node (ref "C10") (pin "2") (pinfunction "2_2") (pintype "passive"))
      (node (ref "C11") (pin "2") (pinfunction "-_2") (pintype "passive"))
      (node (ref "C12") (pin "2") (pinfunction "2_2") (pintype "passive"))
      (node (ref "C13") (pin "2") (pinfunction "2_2") (pintype "passive"))
      (node (ref "C14") (pin "2") (pinfunction "-_2") (pintype "passive"))
      (node (ref "C15") (pin "2") (pinfunction "2_2") (pintype "passive"))
      (node (ref "C16") (pin "2") (pinfunction "2_2") (pintype "passive"))
      (node (ref "C17") (pin "2") (pinfunction "2_2") (pintype "passive"))
      (node (ref "C19") (pin "2") (pinfunction "2_2") (pintype "passive"))
      (node (ref "C2") (pin "2") (pinfunction "2_2") (pintype "passive"))
      (node (ref "C20") (pin "2") (pinfunction "2_2") (pintype "passive"))
      (node (ref "C21") (pin "2") (pinfunction "2_2") (pintype "passive"))
      (node (ref "C22") (pin "2") (pinfunction "2_2") (pintype "passive"))
      (node (ref "C23") (pin "2") (pinfunction "2_2") (pintype "passive"))
      (node (ref "C24") (pin "2") (pinfunction "2_2") (pintype "passive"))
      (node (ref "C25") (pin "2") (pinfunction "2_2") (pintype "passive"))
      (node (ref "C26") (pin "2") (pinfunction "2_2") (pintype "passive"))
      (node (ref "C27") (pin "2") (pinfunction "2_2") (pintype "passive"))
      (node (ref "C28") (pin "2") (pinfunction "2_2") (pintype "passive"))
      (node (ref "C29") (pin "2") (pinfunction "2_2") (pintype "passive"))
      (node (ref "C3") (pin "2") (pinfunction "2_2") (pintype "passive"))
      (node (ref "C30") (pin "2") (pinfunction "2_2") (pintype "passive"))
      (node (ref "C32") (pin "1") (pinfunction "1_1") (pintype "passive"))
      (node (ref "C4") (pin "2") (pinfunction "2_2") (pintype "passive"))
      (node (ref "C5") (pin "2") (pinfunction "2_2") (pintype "passive"))
      (node (ref "C6") (pin "1") (pinfunction "1_1") (pintype "passive"))
      (node (ref "C7") (pin "2") (pinfunction "-_2") (pintype "passive"))
      (node (ref "C8") (pin "1") (pinfunction "1_1") (pintype "passive"))
      (node (ref "C9") (pin "1") (pinfunction "1_1") (pintype "passive"))
      (node (ref "D2") (pin "A") (pinfunction "A_A") (pintype "passive"))
      (node (ref "D3") (pin "1") (pinfunction "A_1") (pintype "passive"))
      (node (ref "D4") (pin "1") (pinfunction "A1_1") (pintype "passive"))
      (node (ref "D5") (pin "1") (pinfunction "A1_1") (pintype "passive"))
      (node (ref "D6") (pin "1") (pinfunction "A1_1") (pintype "passive"))
      (node (ref "ENCODER") (pin "4") (pinfunction "4_4") (pintype "passive"))
      (node (ref "I2C") (pin "1") (pinfunction "1_1") (pintype "passive"))
      (node (ref "IC1") (pin "5") (pinfunction "GND_5") (pintype "bidirectional"))
      (node (ref "IC2") (pin "5") (pinfunction "GND_5") (pintype "passive"))
      (node (ref "IC3") (pin "15") (pinfunction "GND_15") (pintype "bidirectional"))
      (node (ref "IC3") (pin "23") (pinfunction "GND_23") (pintype "bidirectional"))
      (node (ref "IC3") (pin "33") (pinfunction "PE2/~{HWB}_33") (pintype "bidirectional"))
      (node (ref "IC3") (pin "35") (pinfunction "GND_35") (pintype "bidirectional"))
      (node (ref "IC3") (pin "43") (pinfunction "GND_43") (pintype "bidirectional"))
      (node (ref "IC3") (pin "5") (pinfunction "UGND_5") (pintype "bidirectional"))
      (node (ref "IC4") (pin "4") (pinfunction "V-_4") (pintype "power_in"))
      (node (ref "IC5") (pin "4") (pinfunction "V-_4") (pintype "power_in"))
      (node (ref "ISP") (pin "10") (pinfunction "10_10") (pintype "passive"))
      (node (ref "ISP") (pin "4") (pinfunction "4_4") (pintype "passive"))
      (node (ref "ISP") (pin "6") (pinfunction "6_6") (pintype "passive"))
      (node (ref "ISP") (pin "8") (pinfunction "8_8") (pintype "passive"))
      (node (ref "Q1") (pin "2") (pinfunction "E_2") (pintype "passive"))
      (node (ref "Q4") (pin "1") (pinfunction "S_1") (pintype "passive"))
      (node (ref "Q4") (pin "2") (pinfunction "S_2") (pintype "passive"))
      (node (ref "Q4") (pin "3") (pinfunction "S_3") (pintype "passive"))
      (node (ref "Q5") (pin "2") (pinfunction "E_2") (pintype "passive"))
      (node (ref "R1") (pin "1") (pinfunction "1_1") (pintype "passive"))
      (node (ref "R13") (pin "2") (pinfunction "2_2") (pintype "passive"))
      (node (ref "R17") (pin "1") (pinfunction "1_1") (pintype "passive"))
      (node (ref "R19") (pin "1") (pinfunction "1_1") (pintype "passive"))
      (node (ref "R22") (pin "1") (pinfunction "1_1") (pintype "passive"))
      (node (ref "R29") (pin "2") (pinfunction "2_2") (pintype "passive"))
      (node (ref "R30") (pin "2") (pinfunction "2_2") (pintype "passive"))
      (node (ref "R33") (pin "1") (pinfunction "1_1") (pintype "passive"))
      (node (ref "R34") (pin "2") (pinfunction "2_2") (pintype "passive"))
      (node (ref "R48") (pin "2") (pinfunction "2_2") (pintype "passive"))
      (node (ref "RESET") (pin "3") (pinfunction "2_3") (pintype "passive"))
      (node (ref "SJ2") (pin "1") (pinfunction "1_1") (pintype "passive"))
      (node (ref "SJ2") (pin "2") (pinfunction "2_2") (pintype "passive"))
      (node (ref "SJ3") (pin "1") (pinfunction "1_1") (pintype "passive"))
      (node (ref "SJ3") (pin "2") (pinfunction "2_2") (pintype "passive"))
      (node (ref "SOLDER_IRON") (pin "6") (pinfunction "6_6") (pintype "passive"))
      (node (ref "SPI1") (pin "1") (pinfunction "1_1") (pintype "passive"))
      (node (ref "STATUS") (pin "C") (pinfunction "C_C") (pintype "passive"))
      (node (ref "SWITCHES") (pin "4") (pinfunction "4_4") (pintype "passive"))
      (node (ref "U1") (pin "2") (pinfunction "GND_2") (pintype "power_in"))
      (node (ref "USB") (pin "GND") (pinfunction "GND_GND") (pintype "bidirectional"))
      (node (ref "USB_EXT") (pin "4") (pinfunction "4_4") (pintype "passive"))
    )
    (net (code "42") (name "GND1") (class "Default")
      (node (ref "R48") (pin "1") (pinfunction "1_1") (pintype "passive"))
      (node (ref "SOLDER_IRON") (pin "5") (pinfunction "5_5") (pintype "passive"))
    )
    (net (code "43") (name "Net-(+5V_OK-PadA)") (class "Default")
      (node (ref "+5V_OK") (pin "A") (pinfunction "A_A") (pintype "passive"))
      (node (ref "R14") (pin "1") (pinfunction "1_1") (pintype "passive"))
    )
    (net (code "44") (name "Net-(C31-Pad1)") (class "Default")
      (node (ref "C31") (pin "1") (pinfunction "1_1") (pintype "passive"))
      (node (ref "R52") (pin "2") (pinfunction "2_2") (pintype "passive"))
    )
    (net (code "45") (name "Net-(C31-Pad2)") (class "Default")
      (node (ref "C31") (pin "2") (pinfunction "2_2") (pintype "passive"))
      (node (ref "IC1") (pin "3") (pinfunction "IP-_3") (pintype "bidirectional"))
      (node (ref "IC1") (pin "4") (pinfunction "IP-_4") (pintype "bidirectional"))
      (node (ref "Q3") (pin "5") (pinfunction "D_5") (pintype "passive"))
      (node (ref "Q3") (pin "6") (pinfunction "D_6") (pintype "passive"))
      (node (ref "Q3") (pin "7") (pinfunction "D_7") (pintype "passive"))
      (node (ref "Q3") (pin "8") (pinfunction "D_8") (pintype "passive"))
    )
    (net (code "46") (name "Net-(D3-C)") (class "Default")
      (node (ref "D3") (pin "3") (pinfunction "C_3") (pintype "passive"))
      (node (ref "Q4") (pin "4") (pinfunction "G_4") (pintype "passive"))
      (node (ref "R12") (pin "1") (pinfunction "1_1") (pintype "passive"))
    )
    (net (code "47") (name "Net-(D5-C1A2)") (class "Default")
      (node (ref "C20") (pin "1") (pinfunction "1_1") (pintype "passive"))
      (node (ref "D5") (pin "3") (pinfunction "C1A2_3") (pintype "passive"))
      (node (ref "IC5") (pin "3") (pinfunction "+IN_3") (pintype "input"))
      (node (ref "R27") (pin "1") (pinfunction "1_1") (pintype "passive"))
      (node (ref "R29") (pin "1") (pinfunction "1_1") (pintype "passive"))
    )
    (net (code "48") (name "Net-(D6-C1A2)") (class "Default")
      (node (ref "C21") (pin "1") (pinfunction "1_1") (pintype "passive"))
      (node (ref "D6") (pin "3") (pinfunction "C1A2_3") (pintype "passive"))
      (node (ref "IC5") (pin "5") (pinfunction "+IN_5") (pintype "input"))
      (node (ref "R28") (pin "1") (pinfunction "1_1") (pintype "passive"))
      (node (ref "R30") (pin "1") (pinfunction "1_1") (pintype "passive"))
    )
    (net (code "49") (name "Net-(GND-P)") (class "Default")
      (node (ref "GND") (pin "1") (pinfunction "P_1") (pintype "passive"))
      (node (ref "Q4") (pin "5") (pinfunction "D_5") (pintype "passive"))
      (node (ref "Q4") (pin "6") (pinfunction "D_6") (pintype "passive"))
      (node (ref "Q4") (pin "7") (pinfunction "D_7") (pintype "passive"))
      (node (ref "Q4") (pin "8") (pinfunction "D_8") (pintype "passive"))
      (node (ref "R11") (pin "2") (pinfunction "2_2") (pintype "passive"))
    )
    (net (code "50") (name "Net-(IC1-FILT)") (class "Default")
      (node (ref "C15") (pin "1") (pinfunction "1_1") (pintype "passive"))
      (node (ref "IC1") (pin "6") (pinfunction "FILT_6") (pintype "bidirectional"))
    )
    (net (code "51") (name "Net-(IC1-VOUT)") (class "Default")
      (node (ref "IC1") (pin "7") (pinfunction "VOUT_7") (pintype "bidirectional"))
      (node (ref "R15") (pin "2") (pinfunction "2_2") (pintype "passive"))
    )
    (net (code "52") (name "Net-(IC2-VIN)") (class "Default")
      (node (ref "C3") (pin "1") (pinfunction "1_1") (pintype "passive"))
      (node (ref "IC2") (pin "1") (pinfunction "/SHDN_1") (pintype "input"))
      (node (ref "IC2") (pin "2") (pinfunction "VIN_2") (pintype "input"))
      (node (ref "L2") (pin "P$2") (pinfunction "2_P$2") (pintype "passive"))
    )
    (net (code "53") (name "Net-(IC3-UCAP)") (class "Default")
      (node (ref "C5") (pin "1") (pinfunction "1_1") (pintype "passive"))
      (node (ref "IC3") (pin "6") (pinfunction "UCAP_6") (pintype "bidirectional"))
    )
    (net (code "54") (name "Net-(IC3-XTAL1)") (class "Default")
      (node (ref "C8") (pin "2") (pinfunction "2_2") (pintype "passive"))
      (node (ref "IC3") (pin "17") (pinfunction "XTAL1_17") (pintype "bidirectional"))
      (node (ref "Y1") (pin "2") (pinfunction "2_2") (pintype "passive"))
    )
    (net (code "55") (name "Net-(IC3-XTAL2)") (class "Default")
      (node (ref "C9") (pin "2") (pinfunction "2_2") (pintype "passive"))
      (node (ref "IC3") (pin "16") (pinfunction "XTAL2_16") (pintype "bidirectional"))
      (node (ref "Y1") (pin "1") (pinfunction "1_1") (pintype "passive"))
    )
    (net (code "56") (name "Net-(IC4A-+IN)") (class "Default")
      (node (ref "IC4") (pin "3") (pinfunction "+IN_3") (pintype "input"))
      (node (ref "R18") (pin "1") (pinfunction "1_1") (pintype "passive"))
      (node (ref "R19") (pin "2") (pinfunction "2_2") (pintype "passive"))
    )
    (net (code "57") (name "Net-(IC4A--IN)") (class "Default")
      (node (ref "C18") (pin "2") (pinfunction "2_2") (pintype "passive"))
      (node (ref "IC4") (pin "2") (pinfunction "-IN_2") (pintype "input"))
      (node (ref "R15") (pin "1") (pinfunction "1_1") (pintype "passive"))
      (node (ref "R21") (pin "2") (pinfunction "2_2") (pintype "passive"))
    )
    (net (code "58") (name "Net-(IC4B--IN)") (class "Default")
      (node (ref "IC4") (pin "6") (pinfunction "-IN_6") (pintype "input"))
      (node (ref "IC4") (pin "7") (pinfunction "OUT_7") (pintype "output"))
    )
    (net (code "59") (name "Net-(IC5A--IN)") (class "Default")
      (node (ref "IC5") (pin "2") (pinfunction "-IN_2") (pintype "input"))
      (node (ref "R33") (pin "2") (pinfunction "2_2") (pintype "passive"))
      (node (ref "R38") (pin "1") (pinfunction "1_1") (pintype "passive"))
    )
    (net (code "60") (name "Net-(IC5A-OUT)") (class "Default")
      (node (ref "IC5") (pin "1") (pinfunction "OUT_1") (pintype "output"))
      (node (ref "R38") (pin "2") (pinfunction "2_2") (pintype "passive"))
      (node (ref "R42") (pin "2") (pinfunction "2_2") (pintype "passive"))
    )
    (net (code "61") (name "Net-(IC5B--IN)") (class "Default")
      (node (ref "IC5") (pin "6") (pinfunction "-IN_6") (pintype "input"))
      (node (ref "R34") (pin "1") (pinfunction "1_1") (pintype "passive"))
      (node (ref "R37") (pin "1") (pinfunction "1_1") (pintype "passive"))
    )
    (net (code "62") (name "Net-(IC5B-OUT)") (class "Default")
      (node (ref "IC5") (pin "7") (pinfunction "OUT_7") (pintype "output"))
      (node (ref "R37") (pin "2") (pinfunction "2_2") (pintype "passive"))
      (node (ref "R41") (pin "2") (pinfunction "2_2") (pintype "passive"))
    )
    (net (code "63") (name "Net-(L1-2)") (class "Default")
      (node (ref "C2") (pin "1") (pinfunction "1_1") (pintype "passive"))
      (node (ref "IC3") (pin "24") (pinfunction "AVCC_24") (pintype "bidirectional"))
      (node (ref "IC3") (pin "44") (pinfunction "AVCC_44") (pintype "bidirectional"))
      (node (ref "L1") (pin "P$2") (pinfunction "2_P$2") (pintype "passive"))
    )
    (net (code "64") (name "Net-(Q1-B)") (class "Default")
      (node (ref "Q1") (pin "1") (pinfunction "B_1") (pintype "passive"))
      (node (ref "R6") (pin "1") (pinfunction "1_1") (pintype "passive"))
    )
    (net (code "65") (name "Net-(Q1-C)") (class "Default")
      (node (ref "D1") (pin "C") (pinfunction "C_C") (pintype "passive"))
      (node (ref "Q1") (pin "3") (pinfunction "C_3") (pintype "passive"))
      (node (ref "Q2") (pin "1") (pinfunction "B_1") (pintype "passive"))
      (node (ref "R9") (pin "2") (pinfunction "2_2") (pintype "passive"))
    )
    (net (code "66") (name "Net-(Q2-E)") (class "Default")
      (node (ref "D1") (pin "A") (pinfunction "A_A") (pintype "passive"))
      (node (ref "Q2") (pin "2") (pinfunction "E_2") (pintype "passive"))
      (node (ref "Q3") (pin "4") (pinfunction "G_4") (pintype "passive"))
    )
    (net (code "67") (name "Net-(Q5-B)") (class "Default")
      (node (ref "Q5") (pin "1") (pinfunction "B_1") (pintype "passive"))
      (node (ref "R23") (pin "1") (pinfunction "1_1") (pintype "passive"))
    )
    (net (code "68") (name "Net-(Q5-C)") (class "Default")
      (node (ref "Q5") (pin "3") (pinfunction "C_3") (pintype "passive"))
      (node (ref "Q6") (pin "1") (pinfunction "G_1") (pintype "passive"))
      (node (ref "R24") (pin "1") (pinfunction "1_1") (pintype "passive"))
    )
    (net (code "69") (name "Net-(Q6-D)") (class "Default")
      (node (ref "Q6") (pin "3") (pinfunction "D_3") (pintype "passive"))
      (node (ref "R26") (pin "2") (pinfunction "2_2") (pintype "passive"))
    )
    (net (code "70") (name "Net-(R2-Pad2)") (class "Default")
      (node (ref "R2") (pin "2") (pinfunction "2_2") (pintype "passive"))
      (node (ref "SJ1") (pin "3") (pinfunction "3_3") (pintype "passive"))
    )
    (net (code "71") (name "Net-(R3-Pad1)") (class "Default")
      (node (ref "R3") (pin "1") (pinfunction "1_1") (pintype "passive"))
      (node (ref "TX_LED") (pin "A") (pinfunction "A_A") (pintype "passive"))
    )
    (net (code "72") (name "Net-(R4-Pad2)") (class "Default")
      (node (ref "R4") (pin "2") (pinfunction "2_2") (pintype "passive"))
      (node (ref "USB") (pin "D+") (pinfunction "D+_D+") (pintype "bidirectional"))
      (node (ref "USB_EXT") (pin "1") (pinfunction "1_1") (pintype "passive"))
    )
    (net (code "73") (name "Net-(R5-Pad2)") (class "Default")
      (node (ref "R5") (pin "2") (pinfunction "2_2") (pintype "passive"))
      (node (ref "USB") (pin "D-") (pinfunction "D-_D-") (pintype "bidirectional"))
      (node (ref "USB_EXT") (pin "2") (pinfunction "2_2") (pintype "passive"))
    )
    (net (code "74") (name "Net-(R7-Pad2)") (class "Default")
      (node (ref "R7") (pin "2") (pinfunction "2_2") (pintype "passive"))
      (node (ref "SJ1") (pin "1") (pinfunction "1_1") (pintype "passive"))
    )
    (net (code "75") (name "Net-(R8-Pad1)") (class "Default")
      (node (ref "R8") (pin "1") (pinfunction "1_1") (pintype "passive"))
      (node (ref "RX_LEX") (pin "A") (pinfunction "A_A") (pintype "passive"))
    )
    (net (code "76") (name "Net-(R16-Pad1)") (class "Default")
      (node (ref "R16") (pin "1") (pinfunction "1_1") (pintype "passive"))
      (node (ref "R17") (pin "2") (pinfunction "2_2") (pintype "passive"))
      (node (ref "R20") (pin "1") (pinfunction "1_1") (pintype "passive"))
    )
    (net (code "77") (name "Net-(R47-Pad1)") (class "Default")
      (node (ref "R47") (pin "1") (pinfunction "1_1") (pintype "passive"))
      (node (ref "STATUS") (pin "A") (pinfunction "A_A") (pintype "passive"))
    )
    (net (code "78") (name "Net-(R49-Pad1)") (class "Default")
      (node (ref "R49") (pin "1") (pinfunction "1_1") (pintype "passive"))
      (node (ref "USB") (pin "VBUS") (pinfunction "VBUS_VBUS") (pintype "bidirectional"))
      (node (ref "USB_EXT") (pin "3") (pinfunction "3_3") (pintype "passive"))
    )
    (net (code "79") (name "Net-(R53-Pad1)") (class "Default")
      (node (ref "R53") (pin "1") (pinfunction "1_1") (pintype "passive"))
      (node (ref "SPI1") (pin "4") (pinfunction "4_4") (pintype "passive"))
    )
    (net (code "80") (name "Net-(R54-Pad1)") (class "Default")
      (node (ref "R54") (pin "1") (pinfunction "1_1") (pintype "passive"))
      (node (ref "SPI1") (pin "5") (pinfunction "5_5") (pintype "passive"))
    )
    (net (code "81") (name "Net-(R55-Pad1)") (class "Default")
      (node (ref "R55") (pin "1") (pinfunction "1_1") (pintype "passive"))
      (node (ref "SPI1") (pin "6") (pinfunction "6_6") (pintype "passive"))
    )
    (net (code "82") (name "Net-(R56-Pad1)") (class "Default")
      (node (ref "R56") (pin "1") (pinfunction "1_1") (pintype "passive"))
      (node (ref "SPI1") (pin "7") (pinfunction "7_7") (pintype "passive"))
    )
    (net (code "83") (name "Net-(R57-Pad1)") (class "Default")
      (node (ref "R57") (pin "1") (pinfunction "1_1") (pintype "passive"))
      (node (ref "SPI1") (pin "8") (pinfunction "8_8") (pintype "passive"))
    )
    (net (code "84") (name "Net-(ROT-PadA)") (class "Default")
      (node (ref "ROT") (pin "A") (pinfunction "A_A") (pintype "bidirectional"))
      (node (ref "USB2") (pin "D+") (pinfunction "D+_D+") (pintype "bidirectional"))
      (node (ref "USB_ENC") (pin "1") (pinfunction "1_1") (pintype "passive"))
    )
    (net (code "85") (name "Net-(ROT-PadB)") (class "Default")
      (node (ref "ROT") (pin "B") (pinfunction "B_B") (pintype "bidirectional"))
      (node (ref "USB2") (pin "D-") (pinfunction "D-_D-") (pintype "bidirectional"))
      (node (ref "USB_ENC") (pin "2") (pinfunction "2_2") (pintype "passive"))
    )
    (net (code "86") (name "Net-(ROT-PadC)") (class "Default")
      (node (ref "ROT") (pin "C") (pinfunction "C_C") (pintype "bidirectional"))
      (node (ref "ROT") (pin "SW-") (pinfunction "SW-_SW-") (pintype "bidirectional"))
      (node (ref "USB2") (pin "GND") (pinfunction "GND_GND") (pintype "bidirectional"))
      (node (ref "USB_ENC") (pin "4") (pinfunction "4_4") (pintype "passive"))
    )
    (net (code "87") (name "Net-(ROT-PadSW+)") (class "Default")
      (node (ref "ROT") (pin "SW+") (pinfunction "SW+_SW+") (pintype "bidirectional"))
      (node (ref "USB2") (pin "VBUS") (pinfunction "VBUS_VBUS") (pintype "bidirectional"))
      (node (ref "USB_ENC") (pin "3") (pinfunction "3_3") (pintype "passive"))
    )
    (net (code "88") (name "Net-(S1-P-Pad3)") (class "Default")
      (node (ref "S1") (pin "3") (pinfunction "P_3") (pintype "passive"))
      (node (ref "S1") (pin "4") (pinfunction "P_4") (pintype "passive"))
      (node (ref "S2") (pin "3") (pinfunction "P_3") (pintype "passive"))
      (node (ref "S2") (pin "4") (pinfunction "P_4") (pintype "passive"))
      (node (ref "S3") (pin "3") (pinfunction "P_3") (pintype "passive"))
      (node (ref "S3") (pin "4") (pinfunction "P_4") (pintype "passive"))
      (node (ref "SW") (pin "4") (pinfunction "4_4") (pintype "passive"))
    )
    (net (code "89") (name "Net-(S1-S-Pad1)") (class "Default")
      (node (ref "S1") (pin "1") (pinfunction "S_1") (pintype "passive"))
      (node (ref "S1") (pin "2") (pinfunction "S_2") (pintype "passive"))
      (node (ref "SW") (pin "1") (pinfunction "1_1") (pintype "passive"))
    )
    (net (code "90") (name "Net-(S2-S-Pad1)") (class "Default")
      (node (ref "S2") (pin "1") (pinfunction "S_1") (pintype "passive"))
      (node (ref "S2") (pin "2") (pinfunction "S_2") (pintype "passive"))
      (node (ref "SW") (pin "2") (pinfunction "2_2") (pintype "passive"))
    )
    (net (code "91") (name "Net-(S3-S-Pad1)") (class "Default")
      (node (ref "S3") (pin "1") (pinfunction "S_1") (pintype "passive"))
      (node (ref "S3") (pin "2") (pinfunction "S_2") (pintype "passive"))
      (node (ref "SW") (pin "3") (pinfunction "3_3") (pintype "passive"))
    )
    (net (code "92") (name "Net-(VCC-P)") (class "Default")
      (node (ref "F1") (pin "1") (pinfunction "1_1") (pintype "passive"))
      (node (ref "VCC") (pin "1") (pinfunction "P_1") (pintype "passive"))
    )
    (net (code "93") (name "PE") (class "Default")
      (node (ref "PE") (pin "1") (pinfunction "P_1") (pintype "passive"))
      (node (ref "R11") (pin "1") (pinfunction "1_1") (pintype "passive"))
      (node (ref "R13") (pin "1") (pinfunction "1_1") (pintype "passive"))
    )
    (net (code "94") (name "UVCC") (class "Default")
      (node (ref "IC3") (pin "2") (pinfunction "UVCC_2") (pintype "bidirectional"))
      (node (ref "IC3") (pin "7") (pinfunction "VBUS_7") (pintype "bidirectional"))
      (node (ref "R49") (pin "2") (pinfunction "2_2") (pintype "passive"))
    )
    (net (code "95") (name "unconnected-(ISP-Pad3)") (class "Default")
      (node (ref "ISP") (pin "3") (pinfunction "3_3") (pintype "passive"))
    )
    (net (code "96") (name "unconnected-(SOLDER_IRON-Pad1)") (class "Default")
      (node (ref "SOLDER_IRON") (pin "1") (pinfunction "1_1") (pintype "passive"))
    )
    (net (code "97") (name "unconnected-(SOLDER_IRON-Pad3)") (class "Default")
      (node (ref "SOLDER_IRON") (pin "3") (pinfunction "3_3") (pintype "passive"))
    )
    (net (code "98") (name "unconnected-(SPI1-Pad9)") (class "Default")
      (node (ref "SPI1") (pin "9") (pinfunction "9_9") (pintype "passive"))
    )
    (net (code "99") (name "unconnected-(SPI1-Pad10)") (class "Default")
      (node (ref "SPI1") (pin "10") (pinfunction "10_10") (pintype "passive"))
    )
  )
)
